# Ethernet_GPS.net
KiCad netlist of a schematic drawn in EasyEDA
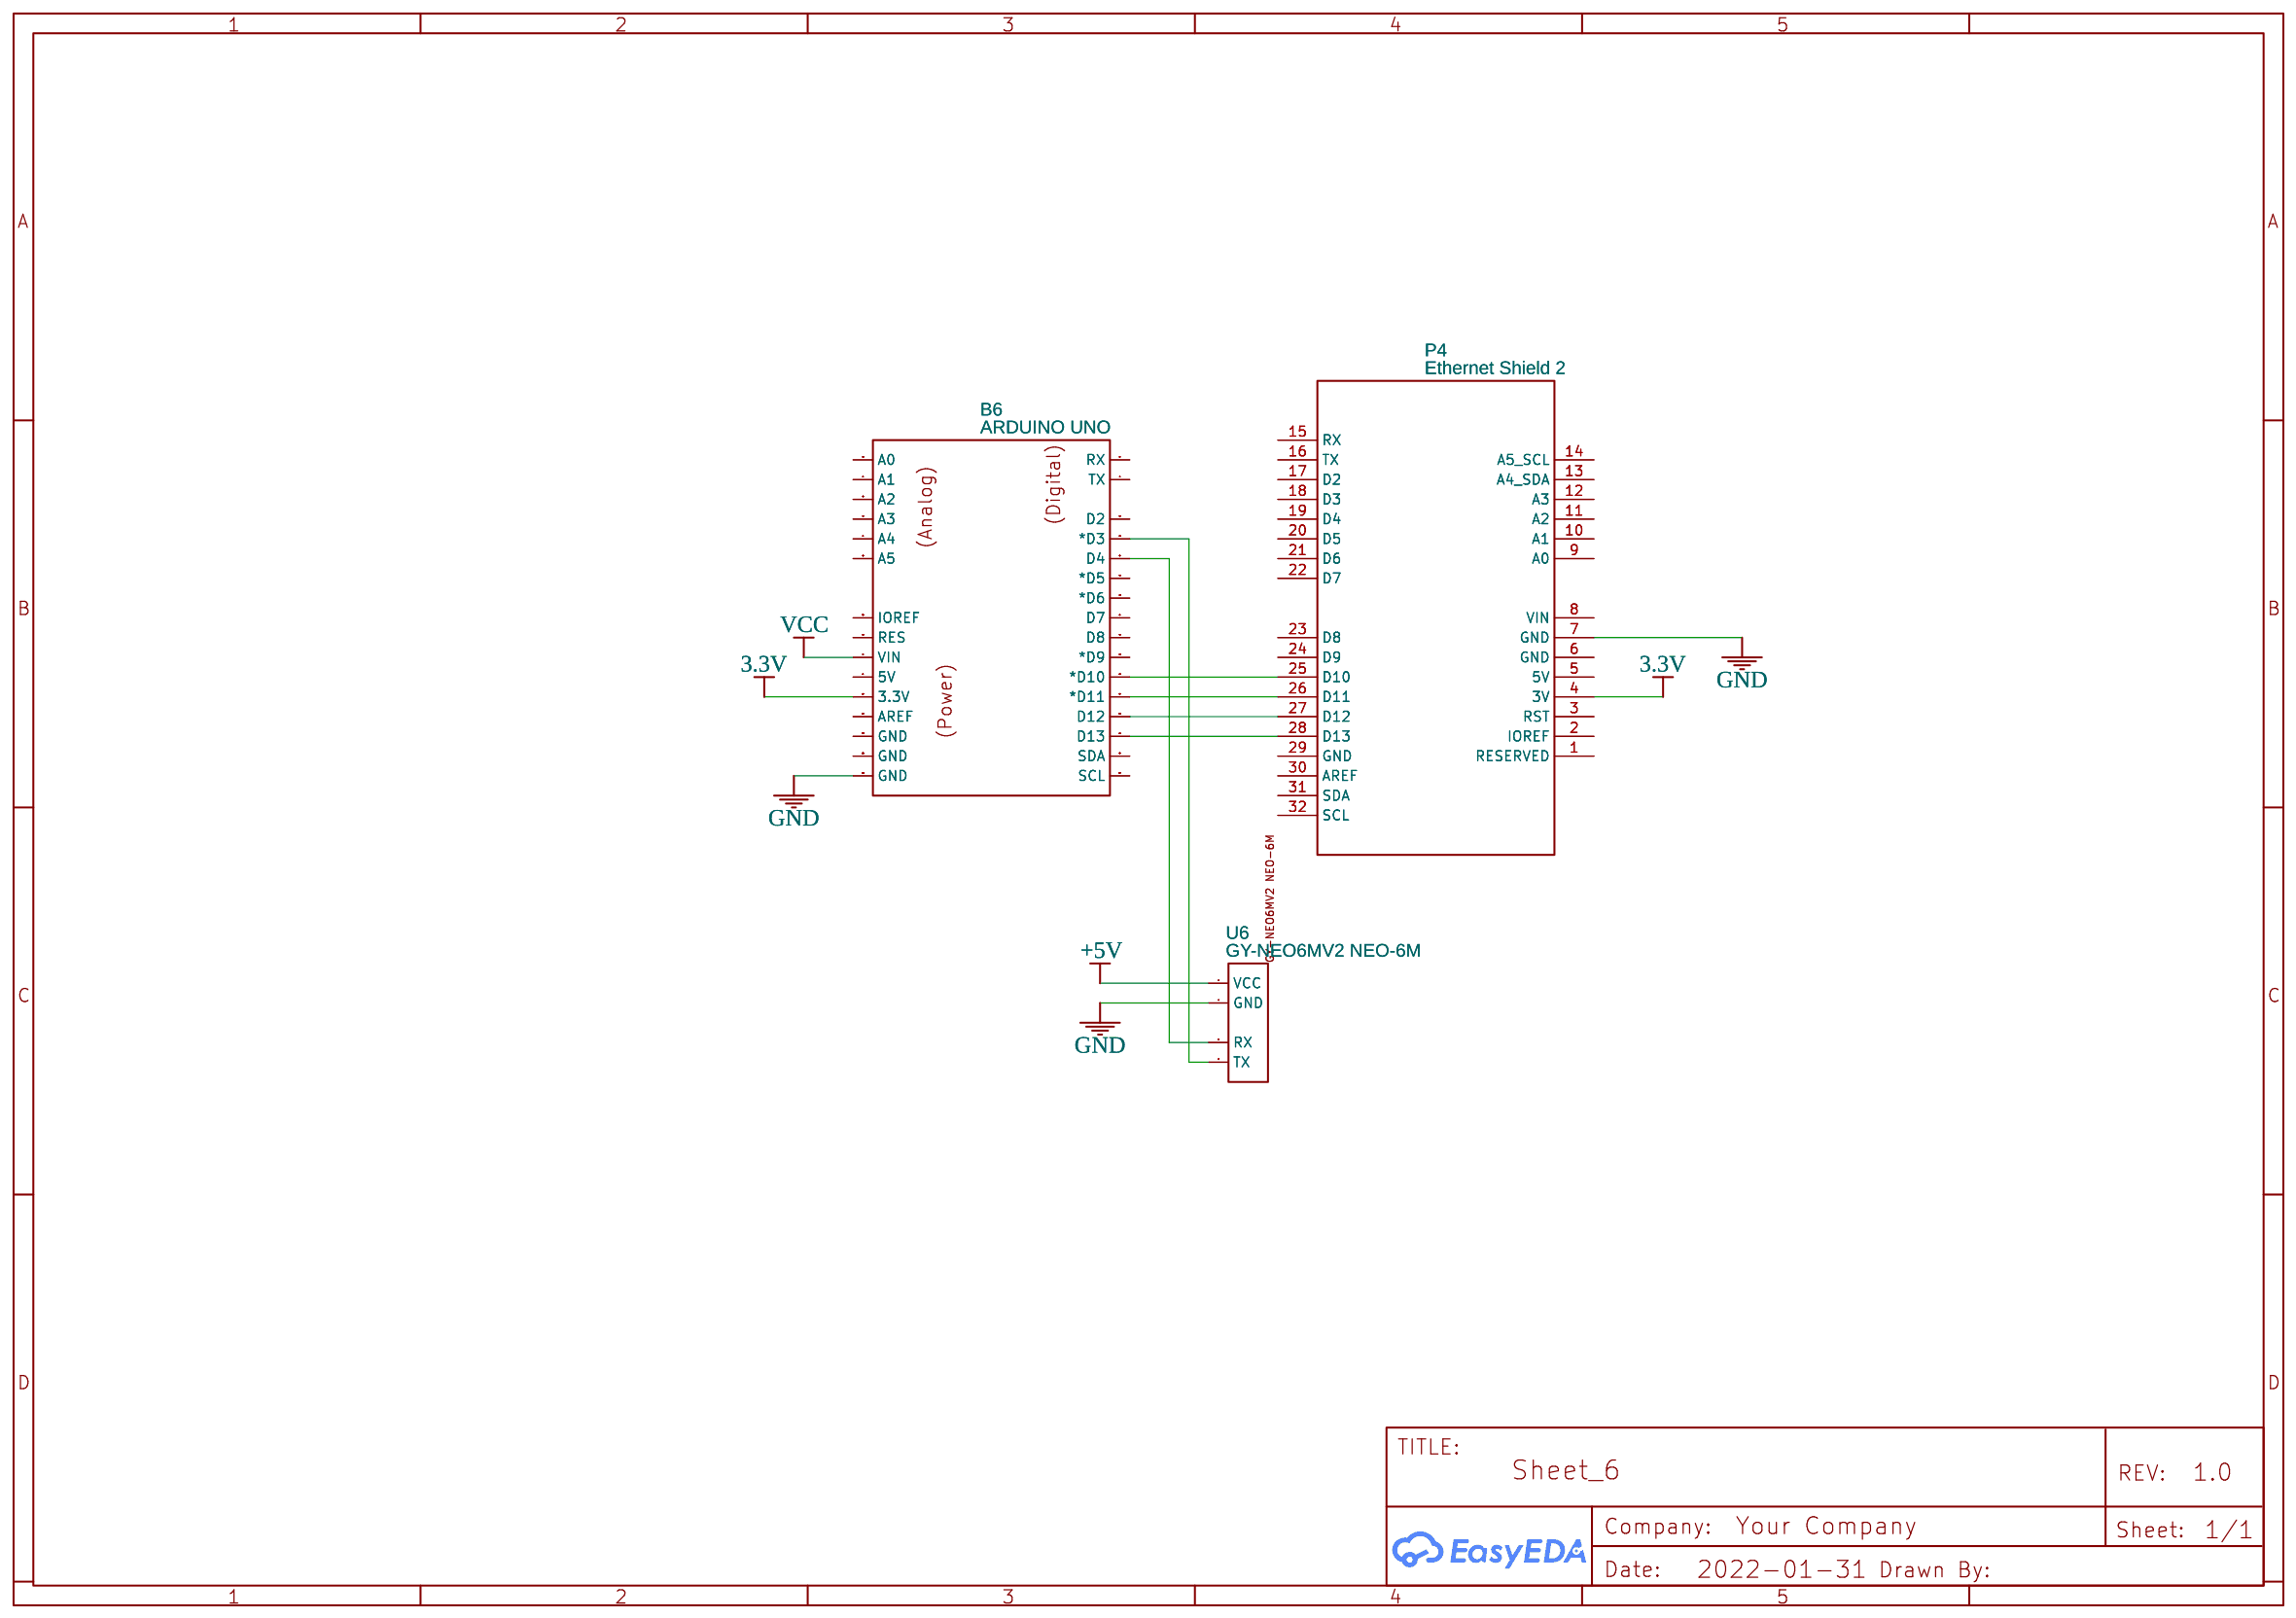
[diagram p0: schematic sheet]

(export (version "E")
  (design (tool "Eeschema 10.0.6"))
  (components
    (comp (ref "B6")
      (value "ARDUINO UNO")
      (fields (field (name "Manufacturer") "?"))
      (libsource (lib "") (part "ARDUINO UNO R3 SHIELD"))
    )
    (comp (ref "P4") (value "Ethernet Shield 2") (libsource (lib "") (part "Ethernet Shield 2")))
    (comp (ref "U6") (value "GY-NEO6MV2 NEO-6M") (libsource (lib "") (part "GY-NEO6MV2 NEO-6M")))
  )
  (nets
    (net (code "1") (name "+5V") (class "Default")
      (node (ref "U6") (pin "4") (pinfunction "VCC_4") (pintype "passive"))
    )
    (net (code "2") (name "3.3V") (class "Default")
      (node (ref "B6") (pin "3.3V") (pinfunction "3.3V_3.3V") (pintype "unspecified"))
      (node (ref "P4") (pin "4") (pinfunction "3V_4") (pintype "unspecified"))
    )
    (net (code "3") (name "GND") (class "Default")
      (node (ref "B6") (pin "GND@0") (pinfunction "GND_GND@0") (pintype "unspecified"))
      (node (ref "P4") (pin "7") (pinfunction "GND_7") (pintype "unspecified"))
      (node (ref "U6") (pin "1") (pinfunction "GND_1") (pintype "output"))
    )
    (net (code "4") (name "Net-(B6-*D3)") (class "Default")
      (node (ref "B6") (pin "D3") (pinfunction "*D3_D3") (pintype "unspecified"))
      (node (ref "U6") (pin "2") (pinfunction "TX_2") (pintype "output"))
    )
    (net (code "5") (name "Net-(B6-*D10)") (class "Default")
      (node (ref "B6") (pin "D10") (pinfunction "*D10_D10") (pintype "unspecified"))
      (node (ref "P4") (pin "25") (pinfunction "D10_25") (pintype "unspecified"))
    )
    (net (code "6") (name "Net-(B6-*D11)") (class "Default")
      (node (ref "B6") (pin "D11") (pinfunction "*D11_D11") (pintype "unspecified"))
      (node (ref "P4") (pin "26") (pinfunction "D11_26") (pintype "unspecified"))
    )
    (net (code "7") (name "Net-(P4-D12)") (class "Default")
      (node (ref "B6") (pin "D12") (pinfunction "D12_D12") (pintype "unspecified"))
      (node (ref "P4") (pin "27") (pinfunction "D12_27") (pintype "unspecified"))
    )
    (net (code "8") (name "Net-(P4-D13)") (class "Default")
      (node (ref "B6") (pin "D13") (pinfunction "D13_D13") (pintype "unspecified"))
      (node (ref "P4") (pin "28") (pinfunction "D13_28") (pintype "unspecified"))
    )
    (net (code "9") (name "Net-(U6-RX)") (class "Default")
      (node (ref "B6") (pin "D4") (pinfunction "D4_D4") (pintype "unspecified"))
      (node (ref "U6") (pin "3") (pinfunction "RX_3") (pintype "input"))
    )
    (net (code "10") (name "VCC") (class "Default")
      (node (ref "B6") (pin "VIN") (pinfunction "VIN_VIN") (pintype "unspecified"))
    )
    (net (code "11") (name "unconnected-(B6-*D5-PadD5)") (class "Default")
      (node (ref "B6") (pin "D5") (pinfunction "*D5_D5") (pintype "unspecified"))
    )
    (net (code "12") (name "unconnected-(B6-*D6-PadD6)") (class "Default")
      (node (ref "B6") (pin "D6") (pinfunction "*D6_D6") (pintype "unspecified"))
    )
    (net (code "13") (name "unconnected-(B6-*D9-PadD9)") (class "Default")
      (node (ref "B6") (pin "D9") (pinfunction "*D9_D9") (pintype "unspecified"))
    )
    (net (code "14") (name "unconnected-(B6-GND-PadGND@1)") (class "Default")
      (node (ref "B6") (pin "GND@1") (pinfunction "GND_GND@1") (pintype "unspecified"))
    )
    (net (code "15") (name "unconnected-(B6-GND-PadGND@2)") (class "Default")
      (node (ref "B6") (pin "GND@2") (pinfunction "GND_GND@2") (pintype "unspecified"))
    )
    (net (code "16") (name "unconnected-(B6-Pad5V)") (class "Default")
      (node (ref "B6") (pin "5V") (pinfunction "5V_5V") (pintype "unspecified"))
    )
    (net (code "17") (name "unconnected-(B6-PadA0)") (class "Default")
      (node (ref "B6") (pin "A0") (pinfunction "A0_A0") (pintype "unspecified"))
    )
    (net (code "18") (name "unconnected-(B6-PadA1)") (class "Default")
      (node (ref "B6") (pin "A1") (pinfunction "A1_A1") (pintype "unspecified"))
    )
    (net (code "19") (name "unconnected-(B6-PadA2)") (class "Default")
      (node (ref "B6") (pin "A2") (pinfunction "A2_A2") (pintype "unspecified"))
    )
    (net (code "20") (name "unconnected-(B6-PadA3)") (class "Default")
      (node (ref "B6") (pin "A3") (pinfunction "A3_A3") (pintype "unspecified"))
    )
    (net (code "21") (name "unconnected-(B6-PadA4)") (class "Default")
      (node (ref "B6") (pin "A4") (pinfunction "A4_A4") (pintype "unspecified"))
    )
    (net (code "22") (name "unconnected-(B6-PadA5)") (class "Default")
      (node (ref "B6") (pin "A5") (pinfunction "A5_A5") (pintype "unspecified"))
    )
    (net (code "23") (name "unconnected-(B6-PadAREF)") (class "Default")
      (node (ref "B6") (pin "AREF") (pinfunction "AREF_AREF") (pintype "unspecified"))
    )
    (net (code "24") (name "unconnected-(B6-PadD2)") (class "Default")
      (node (ref "B6") (pin "D2") (pinfunction "D2_D2") (pintype "unspecified"))
    )
    (net (code "25") (name "unconnected-(B6-PadD7)") (class "Default")
      (node (ref "B6") (pin "D7") (pinfunction "D7_D7") (pintype "unspecified"))
    )
    (net (code "26") (name "unconnected-(B6-PadD8)") (class "Default")
      (node (ref "B6") (pin "D8") (pinfunction "D8_D8") (pintype "unspecified"))
    )
    (net (code "27") (name "unconnected-(B6-PadIOREF)") (class "Default")
      (node (ref "B6") (pin "IOREF") (pinfunction "IOREF_IOREF") (pintype "unspecified"))
    )
    (net (code "28") (name "unconnected-(B6-PadRES)") (class "Default")
      (node (ref "B6") (pin "RES") (pinfunction "RES_RES") (pintype "unspecified"))
    )
    (net (code "29") (name "unconnected-(B6-PadRX)") (class "Default")
      (node (ref "B6") (pin "RX") (pinfunction "RX_RX") (pintype "unspecified"))
    )
    (net (code "30") (name "unconnected-(B6-PadSCL)") (class "Default")
      (node (ref "B6") (pin "SCL") (pinfunction "SCL_SCL") (pintype "unspecified"))
    )
    (net (code "31") (name "unconnected-(B6-PadSDA)") (class "Default")
      (node (ref "B6") (pin "SDA") (pinfunction "SDA_SDA") (pintype "unspecified"))
    )
    (net (code "32") (name "unconnected-(B6-PadTX)") (class "Default")
      (node (ref "B6") (pin "TX") (pinfunction "TX_TX") (pintype "unspecified"))
    )
    (net (code "33") (name "unconnected-(P4-5V-Pad5)") (class "Default")
      (node (ref "P4") (pin "5") (pinfunction "5V_5") (pintype "unspecified"))
    )
    (net (code "34") (name "unconnected-(P4-A0-Pad9)") (class "Default")
      (node (ref "P4") (pin "9") (pinfunction "A0_9") (pintype "unspecified"))
    )
    (net (code "35") (name "unconnected-(P4-A1-Pad10)") (class "Default")
      (node (ref "P4") (pin "10") (pinfunction "A1_10") (pintype "unspecified"))
    )
    (net (code "36") (name "unconnected-(P4-A2-Pad11)") (class "Default")
      (node (ref "P4") (pin "11") (pinfunction "A2_11") (pintype "unspecified"))
    )
    (net (code "37") (name "unconnected-(P4-A3-Pad12)") (class "Default")
      (node (ref "P4") (pin "12") (pinfunction "A3_12") (pintype "unspecified"))
    )
    (net (code "38") (name "unconnected-(P4-A4_SDA-Pad13)") (class "Default")
      (node (ref "P4") (pin "13") (pinfunction "A4_SDA_13") (pintype "unspecified"))
    )
    (net (code "39") (name "unconnected-(P4-A5_SCL-Pad14)") (class "Default")
      (node (ref "P4") (pin "14") (pinfunction "A5_SCL_14") (pintype "unspecified"))
    )
    (net (code "40") (name "unconnected-(P4-AREF-Pad30)") (class "Default")
      (node (ref "P4") (pin "30") (pinfunction "AREF_30") (pintype "unspecified"))
    )
    (net (code "41") (name "unconnected-(P4-D2-Pad17)") (class "Default")
      (node (ref "P4") (pin "17") (pinfunction "D2_17") (pintype "unspecified"))
    )
    (net (code "42") (name "unconnected-(P4-D3-Pad18)") (class "Default")
      (node (ref "P4") (pin "18") (pinfunction "D3_18") (pintype "unspecified"))
    )
    (net (code "43") (name "unconnected-(P4-D4-Pad19)") (class "Default")
      (node (ref "P4") (pin "19") (pinfunction "D4_19") (pintype "unspecified"))
    )
    (net (code "44") (name "unconnected-(P4-D5-Pad20)") (class "Default")
      (node (ref "P4") (pin "20") (pinfunction "D5_20") (pintype "unspecified"))
    )
    (net (code "45") (name "unconnected-(P4-D6-Pad21)") (class "Default")
      (node (ref "P4") (pin "21") (pinfunction "D6_21") (pintype "unspecified"))
    )
    (net (code "46") (name "unconnected-(P4-D7-Pad22)") (class "Default")
      (node (ref "P4") (pin "22") (pinfunction "D7_22") (pintype "unspecified"))
    )
    (net (code "47") (name "unconnected-(P4-D8-Pad23)") (class "Default")
      (node (ref "P4") (pin "23") (pinfunction "D8_23") (pintype "unspecified"))
    )
    (net (code "48") (name "unconnected-(P4-D9-Pad24)") (class "Default")
      (node (ref "P4") (pin "24") (pinfunction "D9_24") (pintype "unspecified"))
    )
    (net (code "49") (name "unconnected-(P4-GND-Pad6)") (class "Default")
      (node (ref "P4") (pin "6") (pinfunction "GND_6") (pintype "unspecified"))
    )
    (net (code "50") (name "unconnected-(P4-GND-Pad29)") (class "Default")
      (node (ref "P4") (pin "29") (pinfunction "GND_29") (pintype "unspecified"))
    )
    (net (code "51") (name "unconnected-(P4-IOREF-Pad2)") (class "Default")
      (node (ref "P4") (pin "2") (pinfunction "IOREF_2") (pintype "unspecified"))
    )
    (net (code "52") (name "unconnected-(P4-RESERVED-Pad1)") (class "Default")
      (node (ref "P4") (pin "1") (pinfunction "RESERVED_1") (pintype "unspecified"))
    )
    (net (code "53") (name "unconnected-(P4-RST-Pad3)") (class "Default")
      (node (ref "P4") (pin "3") (pinfunction "RST_3") (pintype "unspecified"))
    )
    (net (code "54") (name "unconnected-(P4-RX-Pad15)") (class "Default")
      (node (ref "P4") (pin "15") (pinfunction "RX_15") (pintype "unspecified"))
    )
    (net (code "55") (name "unconnected-(P4-SCL-Pad32)") (class "Default")
      (node (ref "P4") (pin "32") (pinfunction "SCL_32") (pintype "unspecified"))
    )
    (net (code "56") (name "unconnected-(P4-SDA-Pad31)") (class "Default")
      (node (ref "P4") (pin "31") (pinfunction "SDA_31") (pintype "unspecified"))
    )
    (net (code "57") (name "unconnected-(P4-TX-Pad16)") (class "Default")
      (node (ref "P4") (pin "16") (pinfunction "TX_16") (pintype "unspecified"))
    )
    (net (code "58") (name "unconnected-(P4-VIN-Pad8)") (class "Default")
      (node (ref "P4") (pin "8") (pinfunction "VIN_8") (pintype "unspecified"))
    )
  )
)
